# powermeter.net
KiCad netlist of a schematic drawn in EAGLE
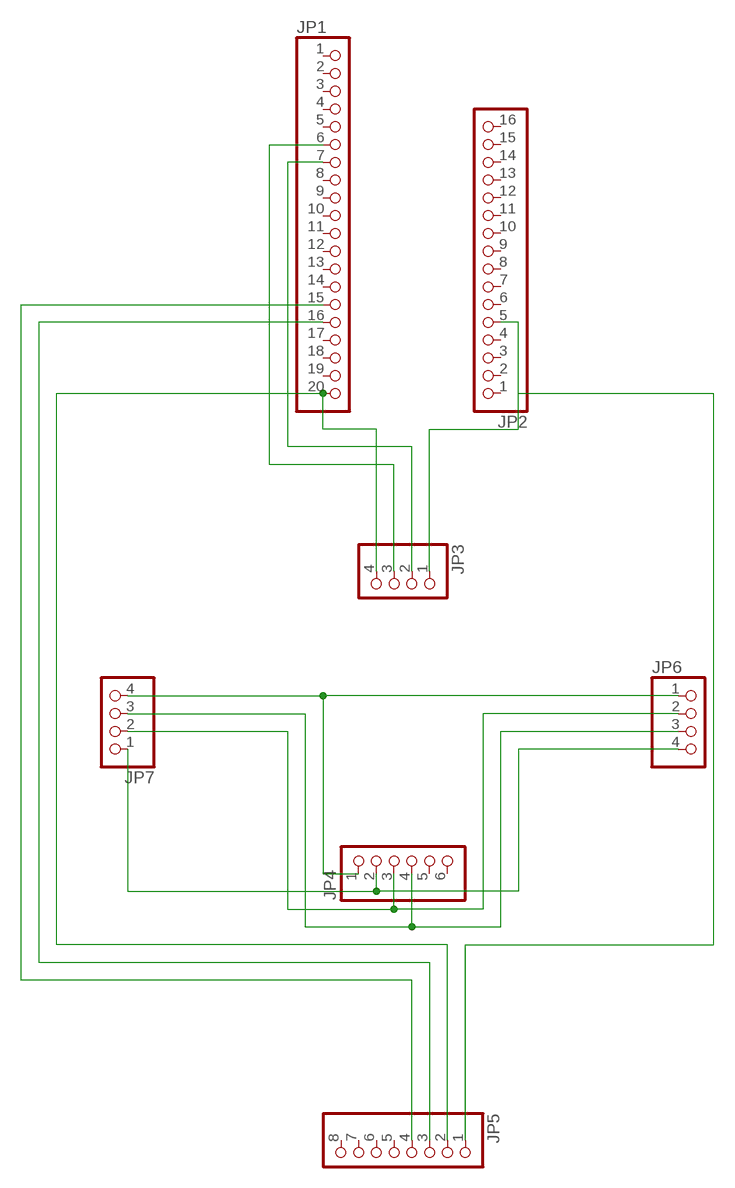
[diagram p0: schematic, sheet 1]

(export (version "E")
  (design (tool "Eeschema 10.0.6"))
  (components
    (comp (ref "JP1")
      (value "PINHD-1X20")
      (footprint "eagle-import:1X20")
      (libsource (lib "eagle-import") (part "PINHD-1X20"))
    )
    (comp (ref "JP2")
      (value "PINHD-1X16")
      (footprint "eagle-import:1X16")
      (libsource (lib "eagle-import") (part "PINHD-1X16"))
    )
    (comp (ref "JP3")
      (value "PINHD-1X4")
      (footprint "eagle-import:1X04")
      (libsource (lib "eagle-import") (part "PINHD-1X4"))
    )
    (comp (ref "JP4")
      (value "PINHD-1X6")
      (footprint "eagle-import:1X06")
      (libsource (lib "eagle-import") (part "PINHD-1X6"))
    )
    (comp (ref "JP5")
      (value "PINHD-1X8")
      (footprint "eagle-import:1X08")
      (libsource (lib "eagle-import") (part "PINHD-1X8"))
    )
    (comp (ref "JP6")
      (value "PINHD-1X4")
      (footprint "eagle-import:1X04")
      (libsource (lib "eagle-import") (part "PINHD-1X4"))
    )
    (comp (ref "JP7")
      (value "PINHD-1X4")
      (footprint "eagle-import:1X04")
      (libsource (lib "eagle-import") (part "PINHD-1X4"))
    )
  )
  (nets
    (net (code "1") (name "Net-(JP1-Pad6)") (class "Default")
      (node (ref "JP1") (pin "6") (pinfunction "6_6") (pintype "passive"))
      (node (ref "JP3") (pin "3") (pinfunction "3_3") (pintype "passive"))
    )
    (net (code "2") (name "Net-(JP1-Pad7)") (class "Default")
      (node (ref "JP1") (pin "7") (pinfunction "7_7") (pintype "passive"))
      (node (ref "JP3") (pin "2") (pinfunction "2_2") (pintype "passive"))
    )
    (net (code "3") (name "Net-(JP1-Pad15)") (class "Default")
      (node (ref "JP1") (pin "15") (pinfunction "15_15") (pintype "passive"))
      (node (ref "JP5") (pin "4") (pinfunction "4_4") (pintype "passive"))
    )
    (net (code "4") (name "Net-(JP1-Pad16)") (class "Default")
      (node (ref "JP1") (pin "16") (pinfunction "16_16") (pintype "passive"))
      (node (ref "JP5") (pin "3") (pinfunction "3_3") (pintype "passive"))
    )
    (net (code "5") (name "Net-(JP1-Pad20)") (class "Default")
      (node (ref "JP1") (pin "20") (pinfunction "20_20") (pintype "passive"))
      (node (ref "JP3") (pin "4") (pinfunction "4_4") (pintype "passive"))
      (node (ref "JP5") (pin "2") (pinfunction "2_2") (pintype "passive"))
    )
    (net (code "6") (name "Net-(JP2-Pad5)") (class "Default")
      (node (ref "JP2") (pin "5") (pinfunction "5_5") (pintype "passive"))
      (node (ref "JP3") (pin "1") (pinfunction "1_1") (pintype "passive"))
      (node (ref "JP5") (pin "1") (pinfunction "1_1") (pintype "passive"))
    )
    (net (code "7") (name "Net-(JP4-Pad1)") (class "Default")
      (node (ref "JP4") (pin "1") (pinfunction "1_1") (pintype "passive"))
      (node (ref "JP6") (pin "1") (pinfunction "1_1") (pintype "passive"))
      (node (ref "JP7") (pin "4") (pinfunction "4_4") (pintype "passive"))
    )
    (net (code "8") (name "Net-(JP4-Pad2)") (class "Default")
      (node (ref "JP4") (pin "2") (pinfunction "2_2") (pintype "passive"))
      (node (ref "JP6") (pin "4") (pinfunction "4_4") (pintype "passive"))
      (node (ref "JP7") (pin "1") (pinfunction "1_1") (pintype "passive"))
    )
    (net (code "9") (name "Net-(JP4-Pad3)") (class "Default")
      (node (ref "JP4") (pin "3") (pinfunction "3_3") (pintype "passive"))
      (node (ref "JP6") (pin "2") (pinfunction "2_2") (pintype "passive"))
      (node (ref "JP7") (pin "2") (pinfunction "2_2") (pintype "passive"))
    )
    (net (code "10") (name "Net-(JP4-Pad4)") (class "Default")
      (node (ref "JP4") (pin "4") (pinfunction "4_4") (pintype "passive"))
      (node (ref "JP6") (pin "3") (pinfunction "3_3") (pintype "passive"))
      (node (ref "JP7") (pin "3") (pinfunction "3_3") (pintype "passive"))
    )
    (net (code "11") (name "unconnected-(JP1-Pad1)") (class "Default")
      (node (ref "JP1") (pin "1") (pinfunction "1_1") (pintype "passive"))
    )
    (net (code "12") (name "unconnected-(JP1-Pad2)") (class "Default")
      (node (ref "JP1") (pin "2") (pinfunction "2_2") (pintype "passive"))
    )
    (net (code "13") (name "unconnected-(JP1-Pad3)") (class "Default")
      (node (ref "JP1") (pin "3") (pinfunction "3_3") (pintype "passive"))
    )
    (net (code "14") (name "unconnected-(JP1-Pad4)") (class "Default")
      (node (ref "JP1") (pin "4") (pinfunction "4_4") (pintype "passive"))
    )
    (net (code "15") (name "unconnected-(JP1-Pad5)") (class "Default")
      (node (ref "JP1") (pin "5") (pinfunction "5_5") (pintype "passive"))
    )
    (net (code "16") (name "unconnected-(JP1-Pad8)") (class "Default")
      (node (ref "JP1") (pin "8") (pinfunction "8_8") (pintype "passive"))
    )
    (net (code "17") (name "unconnected-(JP1-Pad9)") (class "Default")
      (node (ref "JP1") (pin "9") (pinfunction "9_9") (pintype "passive"))
    )
    (net (code "18") (name "unconnected-(JP1-Pad10)") (class "Default")
      (node (ref "JP1") (pin "10") (pinfunction "10_10") (pintype "passive"))
    )
    (net (code "19") (name "unconnected-(JP1-Pad11)") (class "Default")
      (node (ref "JP1") (pin "11") (pinfunction "11_11") (pintype "passive"))
    )
    (net (code "20") (name "unconnected-(JP1-Pad12)") (class "Default")
      (node (ref "JP1") (pin "12") (pinfunction "12_12") (pintype "passive"))
    )
    (net (code "21") (name "unconnected-(JP1-Pad13)") (class "Default")
      (node (ref "JP1") (pin "13") (pinfunction "13_13") (pintype "passive"))
    )
    (net (code "22") (name "unconnected-(JP1-Pad14)") (class "Default")
      (node (ref "JP1") (pin "14") (pinfunction "14_14") (pintype "passive"))
    )
    (net (code "23") (name "unconnected-(JP1-Pad17)") (class "Default")
      (node (ref "JP1") (pin "17") (pinfunction "17_17") (pintype "passive"))
    )
    (net (code "24") (name "unconnected-(JP1-Pad18)") (class "Default")
      (node (ref "JP1") (pin "18") (pinfunction "18_18") (pintype "passive"))
    )
    (net (code "25") (name "unconnected-(JP1-Pad19)") (class "Default")
      (node (ref "JP1") (pin "19") (pinfunction "19_19") (pintype "passive"))
    )
    (net (code "26") (name "unconnected-(JP2-Pad1)") (class "Default")
      (node (ref "JP2") (pin "1") (pinfunction "1_1") (pintype "passive"))
    )
    (net (code "27") (name "unconnected-(JP2-Pad2)") (class "Default")
      (node (ref "JP2") (pin "2") (pinfunction "2_2") (pintype "passive"))
    )
    (net (code "28") (name "unconnected-(JP2-Pad3)") (class "Default")
      (node (ref "JP2") (pin "3") (pinfunction "3_3") (pintype "passive"))
    )
    (net (code "29") (name "unconnected-(JP2-Pad4)") (class "Default")
      (node (ref "JP2") (pin "4") (pinfunction "4_4") (pintype "passive"))
    )
    (net (code "30") (name "unconnected-(JP2-Pad6)") (class "Default")
      (node (ref "JP2") (pin "6") (pinfunction "6_6") (pintype "passive"))
    )
    (net (code "31") (name "unconnected-(JP2-Pad7)") (class "Default")
      (node (ref "JP2") (pin "7") (pinfunction "7_7") (pintype "passive"))
    )
    (net (code "32") (name "unconnected-(JP2-Pad8)") (class "Default")
      (node (ref "JP2") (pin "8") (pinfunction "8_8") (pintype "passive"))
    )
    (net (code "33") (name "unconnected-(JP2-Pad9)") (class "Default")
      (node (ref "JP2") (pin "9") (pinfunction "9_9") (pintype "passive"))
    )
    (net (code "34") (name "unconnected-(JP2-Pad10)") (class "Default")
      (node (ref "JP2") (pin "10") (pinfunction "10_10") (pintype "passive"))
    )
    (net (code "35") (name "unconnected-(JP2-Pad11)") (class "Default")
      (node (ref "JP2") (pin "11") (pinfunction "11_11") (pintype "passive"))
    )
    (net (code "36") (name "unconnected-(JP2-Pad12)") (class "Default")
      (node (ref "JP2") (pin "12") (pinfunction "12_12") (pintype "passive"))
    )
    (net (code "37") (name "unconnected-(JP2-Pad13)") (class "Default")
      (node (ref "JP2") (pin "13") (pinfunction "13_13") (pintype "passive"))
    )
    (net (code "38") (name "unconnected-(JP2-Pad14)") (class "Default")
      (node (ref "JP2") (pin "14") (pinfunction "14_14") (pintype "passive"))
    )
    (net (code "39") (name "unconnected-(JP2-Pad15)") (class "Default")
      (node (ref "JP2") (pin "15") (pinfunction "15_15") (pintype "passive"))
    )
    (net (code "40") (name "unconnected-(JP2-Pad16)") (class "Default")
      (node (ref "JP2") (pin "16") (pinfunction "16_16") (pintype "passive"))
    )
    (net (code "41") (name "unconnected-(JP4-Pad5)") (class "Default")
      (node (ref "JP4") (pin "5") (pinfunction "5_5") (pintype "passive"))
    )
    (net (code "42") (name "unconnected-(JP4-Pad6)") (class "Default")
      (node (ref "JP4") (pin "6") (pinfunction "6_6") (pintype "passive"))
    )
    (net (code "43") (name "unconnected-(JP5-Pad5)") (class "Default")
      (node (ref "JP5") (pin "5") (pinfunction "5_5") (pintype "passive"))
    )
    (net (code "44") (name "unconnected-(JP5-Pad6)") (class "Default")
      (node (ref "JP5") (pin "6") (pinfunction "6_6") (pintype "passive"))
    )
    (net (code "45") (name "unconnected-(JP5-Pad7)") (class "Default")
      (node (ref "JP5") (pin "7") (pinfunction "7_7") (pintype "passive"))
    )
    (net (code "46") (name "unconnected-(JP5-Pad8)") (class "Default")
      (node (ref "JP5") (pin "8") (pinfunction "8_8") (pintype "passive"))
    )
  )
)
